# tda2030.net
KiCad netlist of a schematic drawn in EAGLE
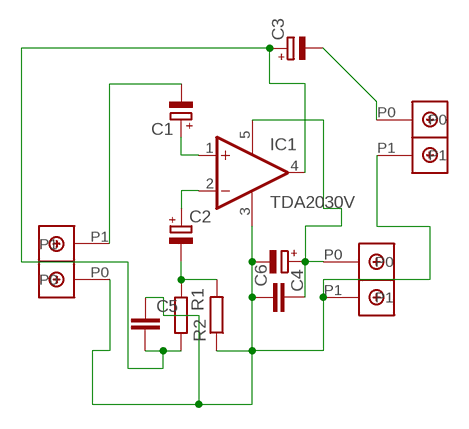
[diagram p0: schematic, sheet 1]

(export (version "E")
  (design (tool "Eeschema 10.0.6"))
  (components
    (comp (ref "12V")
      (value "DBCONN-1X2")
      (footprint "eagle-import:DBCONN-1X2")
      (libsource (lib "eagle-import") (part "DBCONN-1X2"))
    )
    (comp (ref "AUDIOIN")
      (value "DBCONN-1X2")
      (footprint "eagle-import:DBCONN-1X2")
      (libsource (lib "eagle-import") (part "DBCONN-1X2"))
    )
    (comp (ref "C1")
      (value "CPOL-EUE2.5-6")
      (footprint "eagle-import:E2,5-6")
      (libsource (lib "eagle-import") (part "CPOL-EUE2.5-6"))
    )
    (comp (ref "C2")
      (value "CPOL-EUE3.5-8")
      (footprint "eagle-import:E3,5-8")
      (libsource (lib "eagle-import") (part "CPOL-EUE3.5-8"))
    )
    (comp (ref "C3")
      (value "CPOL-EUE3.5-10")
      (footprint "eagle-import:E3,5-10")
      (libsource (lib "eagle-import") (part "CPOL-EUE3.5-10"))
    )
    (comp (ref "C4")
      (value "CPOL-EUE3.5-10")
      (footprint "eagle-import:E3,5-10")
      (libsource (lib "eagle-import") (part "CPOL-EUE3.5-10"))
    )
    (comp (ref "C5")
      (value "C-EU050-025X075")
      (footprint "eagle-import:C050-025X075")
      (libsource (lib "eagle-import") (part "C-EU050-025X075"))
    )
    (comp (ref "C6")
      (value "C-EU050-025X075")
      (footprint "eagle-import:C050-025X075")
      (libsource (lib "eagle-import") (part "C-EU050-025X075"))
    )
    (comp (ref "IC1")
      (value "TDA2030V")
      (footprint "eagle-import:CB360")
      (libsource (lib "eagle-import") (part "TDA2030V"))
    )
    (comp (ref "R1")
      (value "R-EU_0204/7")
      (footprint "eagle-import:0204_7")
      (libsource (lib "eagle-import") (part "R-EU_0204/7"))
    )
    (comp (ref "R2")
      (value "R-EU_0204/2V")
      (footprint "eagle-import:0204V")
      (libsource (lib "eagle-import") (part "R-EU_0204/2V"))
    )
    (comp (ref "SPEAKER")
      (value "DBCONN-1X2")
      (footprint "eagle-import:DBCONN-1X2")
      (libsource (lib "eagle-import") (part "DBCONN-1X2"))
    )
  )
  (nets
    (net (code "1") (name "Net-(AUDIOIN-PadP1)") (class "Default")
      (node (ref "AUDIOIN") (pin "P1") (pinfunction "P1_P1") (pintype "bidirectional"))
      (node (ref "C1") (pin "-") (pinfunction "-_-") (pintype "passive"))
    )
    (net (code "2") (name "Net-(C2-Pad-)") (class "Default")
      (node (ref "C2") (pin "-") (pinfunction "-_-") (pintype "passive"))
      (node (ref "R1") (pin "1") (pinfunction "1_1") (pintype "passive"))
      (node (ref "R2") (pin "2") (pinfunction "2_2") (pintype "passive"))
    )
    (net (code "3") (name "Net-(C3-Pad-)") (class "Default")
      (node (ref "C3") (pin "-") (pinfunction "-_-") (pintype "passive"))
      (node (ref "SPEAKER") (pin "P0") (pinfunction "P0_P0") (pintype "bidirectional"))
    )
    (net (code "4") (name "Net-(IC1-+IN)") (class "Default")
      (node (ref "C1") (pin "+") (pinfunction "+_+") (pintype "passive"))
      (node (ref "IC1") (pin "1") (pinfunction "+IN_1") (pintype "input"))
    )
    (net (code "5") (name "Net-(IC1--IN)") (class "Default")
      (node (ref "C2") (pin "+") (pinfunction "+_+") (pintype "passive"))
      (node (ref "IC1") (pin "2") (pinfunction "-IN_2") (pintype "input"))
    )
    (net (code "6") (name "Net-(IC1-GND)") (class "Default")
      (node (ref "12V") (pin "P1") (pinfunction "P1_P1") (pintype "bidirectional"))
      (node (ref "AUDIOIN") (pin "P0") (pinfunction "P0_P0") (pintype "bidirectional"))
      (node (ref "C4") (pin "-") (pinfunction "-_-") (pintype "passive"))
      (node (ref "C5") (pin "1") (pinfunction "1_1") (pintype "passive"))
      (node (ref "C6") (pin "1") (pinfunction "1_1") (pintype "passive"))
      (node (ref "IC1") (pin "3") (pinfunction "GND_3") (pintype "power_in"))
      (node (ref "R2") (pin "1") (pinfunction "1_1") (pintype "passive"))
      (node (ref "SPEAKER") (pin "P1") (pinfunction "P1_P1") (pintype "bidirectional"))
    )
    (net (code "7") (name "Net-(IC1-OUT)") (class "Default")
      (node (ref "C3") (pin "+") (pinfunction "+_+") (pintype "passive"))
      (node (ref "C5") (pin "2") (pinfunction "2_2") (pintype "passive"))
      (node (ref "IC1") (pin "4") (pinfunction "OUT_4") (pintype "output"))
      (node (ref "R1") (pin "2") (pinfunction "2_2") (pintype "passive"))
    )
    (net (code "8") (name "Net-(IC1-V+)") (class "Default")
      (node (ref "12V") (pin "P0") (pinfunction "P0_P0") (pintype "bidirectional"))
      (node (ref "C4") (pin "+") (pinfunction "+_+") (pintype "passive"))
      (node (ref "C6") (pin "2") (pinfunction "2_2") (pintype "passive"))
      (node (ref "IC1") (pin "5") (pinfunction "V+_5") (pintype "power_in"))
    )
  )
)
